# Arduino-DUE-V03.net
KiCad netlist of a schematic drawn in EAGLE
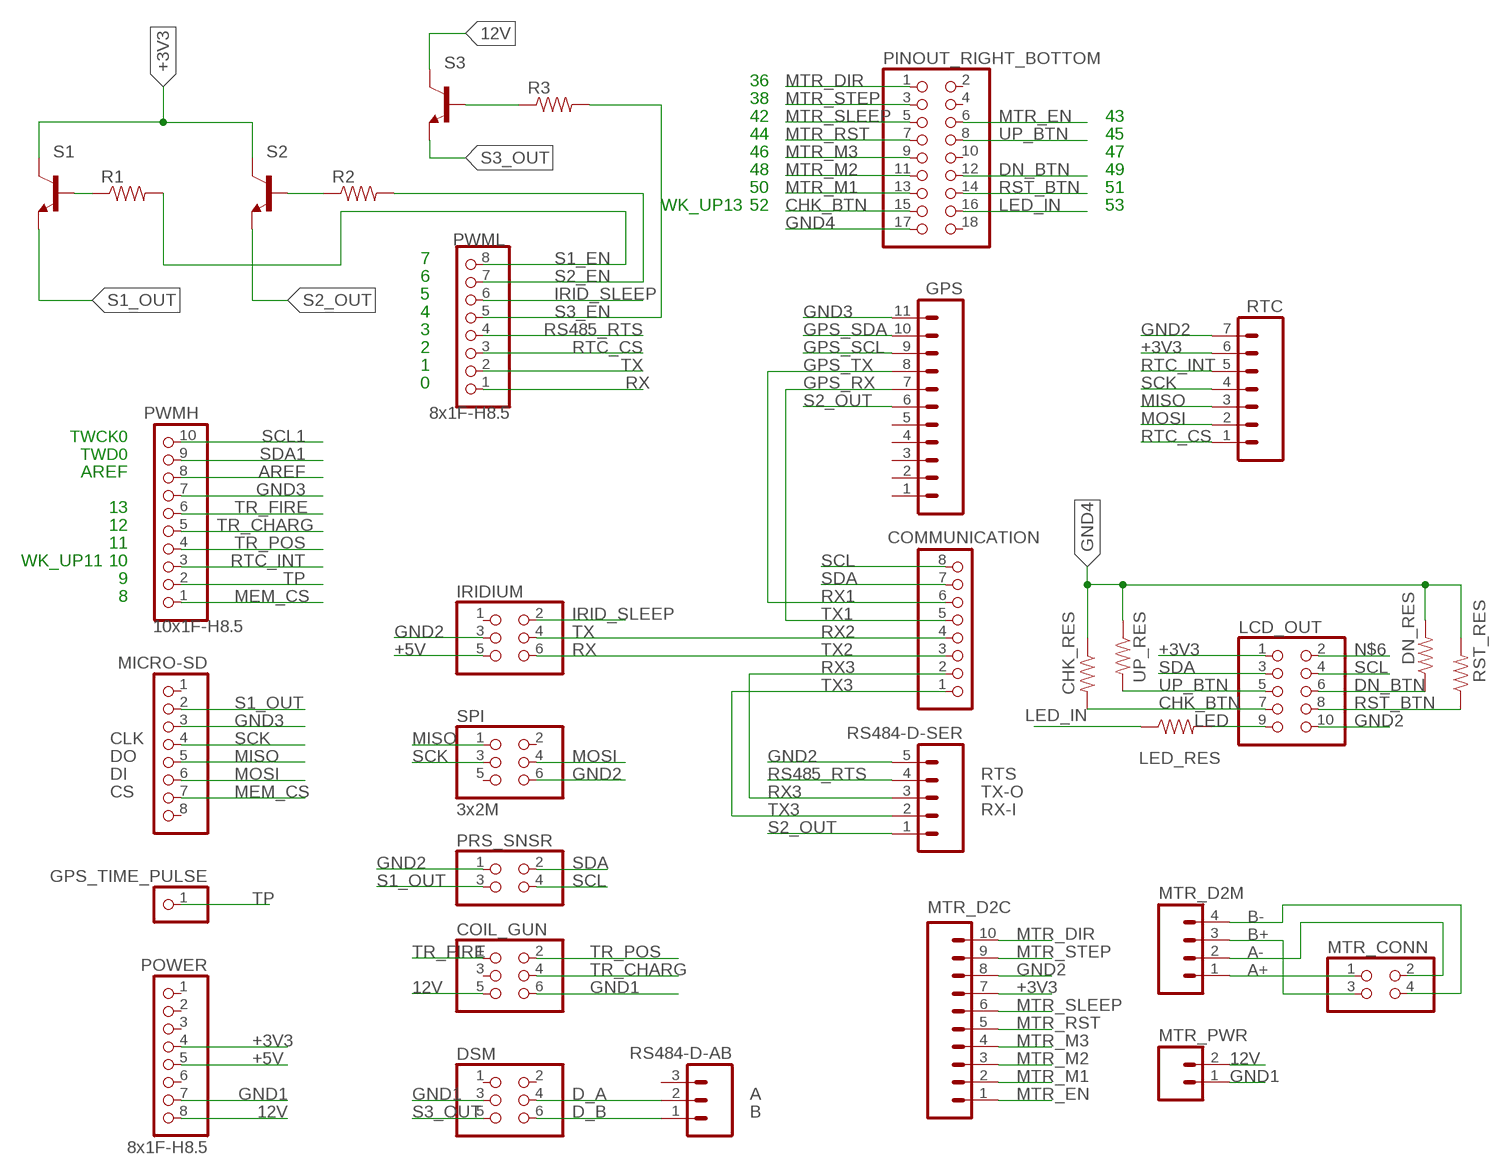
[diagram p0: schematic, sheet 1]

(export (version "E")
  (design (tool "Eeschema 10.0.6"))
  (components
    (comp (ref "CHK_RES")
      (value "RESISTORPTH-1/4W")
      (footprint "eagle-import:AXIAL-0.4")
      (libsource (lib "eagle-import") (part "RESISTORPTH-1/4W"))
    )
    (comp (ref "COIL_GUN")
      (value "PINHD-2X3")
      (footprint "eagle-import:2X03")
      (libsource (lib "eagle-import") (part "pinhead_PINHD-2X3"))
    )
    (comp (ref "COMMUNICATION")
      (value "8x1F-H8.5")
      (footprint "eagle-import:1X08")
      (libsource (lib "eagle-import") (part "PINHD-1X8"))
    )
    (comp (ref "DN_RES")
      (value "RESISTORPTH-1/4W")
      (footprint "eagle-import:AXIAL-0.4")
      (libsource (lib "eagle-import") (part "RESISTORPTH-1/4W"))
    )
    (comp (ref "DSM")
      (value "PINHD-2X3")
      (footprint "eagle-import:2X03")
      (libsource (lib "eagle-import") (part "pinhead_PINHD-2X3"))
    )
    (comp (ref "GPS")
      (value "M111.27MM")
      (footprint "eagle-import:1X11-1.27MM")
      (libsource (lib "eagle-import") (part "M111.27MM"))
    )
    (comp (ref "GPS_TIME_PULSE")
      (value "PINHD-1X1")
      (footprint "eagle-import:1X01")
      (libsource (lib "eagle-import") (part "PINHD-1X1"))
    )
    (comp (ref "IRIDIUM")
      (value "PINHD-2X3")
      (footprint "eagle-import:2X03")
      (libsource (lib "eagle-import") (part "pinhead_PINHD-2X3"))
    )
    (comp (ref "LCD_OUT")
      (value "PINHD-2X5")
      (footprint "eagle-import:2X05")
      (libsource (lib "eagle-import") (part "PINHD-2X5"))
    )
    (comp (ref "LED_RES")
      (value "RESISTORPTH-1/4W")
      (footprint "eagle-import:AXIAL-0.4")
      (libsource (lib "eagle-import") (part "RESISTORPTH-1/4W"))
    )
    (comp (ref "MICRO-SD")
      (value "PINHD-1X8BIG")
      (footprint "eagle-import:1X08-BIG")
      (libsource (lib "eagle-import") (part "PINHD-1X8BIG"))
    )
    (comp (ref "MTR_CONN")
      (value "PINHD-2X2")
      (footprint "eagle-import:2X02")
      (libsource (lib "eagle-import") (part "PINHD-2X2"))
    )
    (comp (ref "MTR_D2C")
      (value "M10SILK_FEMALE_PTH")
      (footprint "eagle-import:1X10")
      (libsource (lib "eagle-import") (part "M10SILK_FEMALE_PTH"))
    )
    (comp (ref "MTR_D2M")
      (value "M04NO_SILK_ALL_ROUND")
      (footprint "eagle-import:1X04_NO_SILK_ALL_ROUND")
      (libsource (lib "eagle-import") (part "M04NO_SILK_ALL_ROUND"))
    )
    (comp (ref "MTR_PWR")
      (value "M02PTH")
      (footprint "eagle-import:1X02")
      (libsource (lib "eagle-import") (part "M02PTH"))
    )
    (comp (ref "PINOUT_RIGHT_BOTTOM")
      (value "PINHD-2X9")
      (footprint "eagle-import:2X09")
      (libsource (lib "eagle-import") (part "PINHD-2X9"))
    )
    (comp (ref "POWER")
      (value "8x1F-H8.5")
      (footprint "eagle-import:1X08")
      (libsource (lib "eagle-import") (part "PINHD-1X8"))
    )
    (comp (ref "PRS_SNSR")
      (value "PINHD-2X2")
      (footprint "eagle-import:2X02")
      (libsource (lib "eagle-import") (part "PINHD-2X2"))
    )
    (comp (ref "PWMH")
      (value "10x1F-H8.5")
      (footprint "eagle-import:1X10")
      (libsource (lib "eagle-import") (part "PINHD-1X10"))
    )
    (comp (ref "PWML")
      (value "8x1F-H8.5")
      (footprint "eagle-import:1X08")
      (libsource (lib "eagle-import") (part "PINHD-1X8"))
    )
    (comp (ref "R1")
      (value "RESISTORPTH-1/4W")
      (footprint "eagle-import:AXIAL-0.4")
      (libsource (lib "eagle-import") (part "RESISTORPTH-1/4W"))
    )
    (comp (ref "R2")
      (value "RESISTORPTH-1/4W")
      (footprint "eagle-import:AXIAL-0.4")
      (libsource (lib "eagle-import") (part "RESISTORPTH-1/4W"))
    )
    (comp (ref "R3")
      (value "RESISTORPTH-1/4W")
      (footprint "eagle-import:AXIAL-0.4")
      (libsource (lib "eagle-import") (part "RESISTORPTH-1/4W"))
    )
    (comp (ref "RS484-D-AB")
      (value "M03PTH")
      (footprint "eagle-import:1X03")
      (libsource (lib "eagle-import") (part "M03PTH"))
    )
    (comp (ref "RS484-D-SER")
      (value "M05PTH")
      (footprint "eagle-import:1X05")
      (libsource (lib "eagle-import") (part "M05PTH"))
    )
    (comp (ref "RST_RES")
      (value "RESISTORPTH-1/4W")
      (footprint "eagle-import:AXIAL-0.4")
      (libsource (lib "eagle-import") (part "RESISTORPTH-1/4W"))
    )
    (comp (ref "RTC")
      (value "M07")
      (footprint "eagle-import:1X07")
      (libsource (lib "eagle-import") (part "M07"))
    )
    (comp (ref "S1")
      (value "2N3904")
      (footprint "eagle-import:TO92")
      (libsource (lib "eagle-import") (part "2N3904"))
    )
    (comp (ref "S2")
      (value "2N3904")
      (footprint "eagle-import:TO92")
      (libsource (lib "eagle-import") (part "2N3904"))
    )
    (comp (ref "S3")
      (value "2N3904")
      (footprint "eagle-import:TO92")
      (libsource (lib "eagle-import") (part "2N3904"))
    )
    (comp (ref "SPI")
      (value "3x2M")
      (footprint "eagle-import:2X03")
      (libsource (lib "eagle-import") (part "PINHD-2X3"))
    )
    (comp (ref "UP_RES")
      (value "RESISTORPTH-1/4W")
      (footprint "eagle-import:AXIAL-0.4")
      (libsource (lib "eagle-import") (part "RESISTORPTH-1/4W"))
    )
  )
  (nets
    (net (code "1") (name "+3V3") (class "Default")
      (node (ref "LCD_OUT") (pin "1") (pinfunction "1_1") (pintype "passive"))
      (node (ref "MTR_D2C") (pin "7") (pinfunction "7_7") (pintype "passive"))
      (node (ref "POWER") (pin "4") (pinfunction "4_4") (pintype "passive"))
      (node (ref "RTC") (pin "6") (pinfunction "6_6") (pintype "passive"))
      (node (ref "S1") (pin "1") (pinfunction "C_1") (pintype "passive"))
      (node (ref "S2") (pin "1") (pinfunction "C_1") (pintype "passive"))
    )
    (net (code "2") (name "/+5V") (class "Default")
      (node (ref "IRIDIUM") (pin "5") (pinfunction "5_5") (pintype "passive"))
      (node (ref "POWER") (pin "5") (pinfunction "5_5") (pintype "passive"))
    )
    (net (code "3") (name "/A+") (class "Default")
      (node (ref "MTR_CONN") (pin "1") (pinfunction "1_1") (pintype "passive"))
      (node (ref "MTR_D2M") (pin "1") (pinfunction "1_1") (pintype "passive"))
    )
    (net (code "4") (name "/A-") (class "Default")
      (node (ref "MTR_CONN") (pin "2") (pinfunction "2_2") (pintype "passive"))
      (node (ref "MTR_D2M") (pin "2") (pinfunction "2_2") (pintype "passive"))
    )
    (net (code "5") (name "/AREF") (class "Default")
      (node (ref "PWMH") (pin "8") (pinfunction "8_8") (pintype "passive"))
    )
    (net (code "6") (name "/B+") (class "Default")
      (node (ref "MTR_CONN") (pin "3") (pinfunction "3_3") (pintype "passive"))
      (node (ref "MTR_D2M") (pin "3") (pinfunction "3_3") (pintype "passive"))
    )
    (net (code "7") (name "/B-") (class "Default")
      (node (ref "MTR_CONN") (pin "4") (pinfunction "4_4") (pintype "passive"))
      (node (ref "MTR_D2M") (pin "4") (pinfunction "4_4") (pintype "passive"))
    )
    (net (code "8") (name "/CHK_BTN") (class "Default")
      (node (ref "CHK_RES") (pin "P$2") (pinfunction "2_P$2") (pintype "passive"))
      (node (ref "LCD_OUT") (pin "7") (pinfunction "7_7") (pintype "passive"))
      (node (ref "PINOUT_RIGHT_BOTTOM") (pin "15") (pinfunction "15_15") (pintype "passive"))
    )
    (net (code "9") (name "/DN_BTN") (class "Default")
      (node (ref "DN_RES") (pin "P$1") (pinfunction "1_P$1") (pintype "passive"))
      (node (ref "LCD_OUT") (pin "6") (pinfunction "6_6") (pintype "passive"))
      (node (ref "PINOUT_RIGHT_BOTTOM") (pin "12") (pinfunction "12_12") (pintype "passive"))
    )
    (net (code "10") (name "/D_A") (class "Default")
      (node (ref "DSM") (pin "4") (pinfunction "4_4") (pintype "passive"))
      (node (ref "RS484-D-AB") (pin "2") (pinfunction "2_2") (pintype "passive"))
    )
    (net (code "11") (name "/D_B") (class "Default")
      (node (ref "DSM") (pin "6") (pinfunction "6_6") (pintype "passive"))
      (node (ref "RS484-D-AB") (pin "1") (pinfunction "1_1") (pintype "passive"))
    )
    (net (code "12") (name "/GND1") (class "Default")
      (node (ref "COIL_GUN") (pin "6") (pinfunction "6_6") (pintype "passive"))
      (node (ref "DSM") (pin "3") (pinfunction "3_3") (pintype "passive"))
      (node (ref "MTR_PWR") (pin "1") (pinfunction "1_1") (pintype "passive"))
      (node (ref "POWER") (pin "7") (pinfunction "7_7") (pintype "passive"))
    )
    (net (code "13") (name "/GND2") (class "Default")
      (node (ref "IRIDIUM") (pin "3") (pinfunction "3_3") (pintype "passive"))
      (node (ref "LCD_OUT") (pin "10") (pinfunction "10_10") (pintype "passive"))
      (node (ref "MTR_D2C") (pin "8") (pinfunction "8_8") (pintype "passive"))
      (node (ref "PRS_SNSR") (pin "1") (pinfunction "1_1") (pintype "passive"))
      (node (ref "RS484-D-SER") (pin "5") (pinfunction "5_5") (pintype "passive"))
      (node (ref "RTC") (pin "7") (pinfunction "7_7") (pintype "passive"))
      (node (ref "SPI") (pin "6") (pinfunction "6_6") (pintype "passive"))
    )
    (net (code "14") (name "/GND3") (class "Default")
      (node (ref "GPS") (pin "11") (pinfunction "11_11") (pintype "passive"))
      (node (ref "MICRO-SD") (pin "3") (pinfunction "3_3") (pintype "passive"))
      (node (ref "PWMH") (pin "7") (pinfunction "7_7") (pintype "passive"))
    )
    (net (code "15") (name "/GPS_RX") (class "Default")
      (node (ref "COMMUNICATION") (pin "5") (pinfunction "5_5") (pintype "passive"))
      (node (ref "GPS") (pin "7") (pinfunction "7_7") (pintype "passive"))
    )
    (net (code "16") (name "/GPS_SCL") (class "Default")
      (node (ref "GPS") (pin "9") (pinfunction "9_9") (pintype "passive"))
    )
    (net (code "17") (name "/GPS_SDA") (class "Default")
      (node (ref "GPS") (pin "10") (pinfunction "10_10") (pintype "passive"))
    )
    (net (code "18") (name "/GPS_TX") (class "Default")
      (node (ref "COMMUNICATION") (pin "6") (pinfunction "6_6") (pintype "passive"))
      (node (ref "GPS") (pin "8") (pinfunction "8_8") (pintype "passive"))
    )
    (net (code "19") (name "/IRID_SLEEP") (class "Default")
      (node (ref "IRIDIUM") (pin "2") (pinfunction "2_2") (pintype "passive"))
      (node (ref "PWML") (pin "6") (pinfunction "6_6") (pintype "passive"))
    )
    (net (code "20") (name "/LED") (class "Default")
      (node (ref "LCD_OUT") (pin "9") (pinfunction "9_9") (pintype "passive"))
      (node (ref "LED_RES") (pin "P$2") (pinfunction "2_P$2") (pintype "passive"))
    )
    (net (code "21") (name "/LED_IN") (class "Default")
      (node (ref "LED_RES") (pin "P$1") (pinfunction "1_P$1") (pintype "passive"))
      (node (ref "PINOUT_RIGHT_BOTTOM") (pin "16") (pinfunction "16_16") (pintype "passive"))
    )
    (net (code "22") (name "/MEM_CS") (class "Default")
      (node (ref "MICRO-SD") (pin "7") (pinfunction "7_7") (pintype "passive"))
      (node (ref "PWMH") (pin "1") (pinfunction "1_1") (pintype "passive"))
    )
    (net (code "23") (name "/MISO") (class "Default")
      (node (ref "MICRO-SD") (pin "5") (pinfunction "5_5") (pintype "passive"))
      (node (ref "RTC") (pin "3") (pinfunction "3_3") (pintype "passive"))
      (node (ref "SPI") (pin "1") (pinfunction "1_1") (pintype "passive"))
    )
    (net (code "24") (name "/MOSI") (class "Default")
      (node (ref "MICRO-SD") (pin "6") (pinfunction "6_6") (pintype "passive"))
      (node (ref "RTC") (pin "2") (pinfunction "2_2") (pintype "passive"))
      (node (ref "SPI") (pin "4") (pinfunction "4_4") (pintype "passive"))
    )
    (net (code "25") (name "/MTR_DIR") (class "Default")
      (node (ref "MTR_D2C") (pin "10") (pinfunction "10_10") (pintype "passive"))
      (node (ref "PINOUT_RIGHT_BOTTOM") (pin "1") (pinfunction "1_1") (pintype "passive"))
    )
    (net (code "26") (name "/MTR_EN") (class "Default")
      (node (ref "MTR_D2C") (pin "1") (pinfunction "1_1") (pintype "passive"))
      (node (ref "PINOUT_RIGHT_BOTTOM") (pin "6") (pinfunction "6_6") (pintype "passive"))
    )
    (net (code "27") (name "/MTR_M1") (class "Default")
      (node (ref "MTR_D2C") (pin "2") (pinfunction "2_2") (pintype "passive"))
      (node (ref "PINOUT_RIGHT_BOTTOM") (pin "13") (pinfunction "13_13") (pintype "passive"))
    )
    (net (code "28") (name "/MTR_M2") (class "Default")
      (node (ref "MTR_D2C") (pin "3") (pinfunction "3_3") (pintype "passive"))
      (node (ref "PINOUT_RIGHT_BOTTOM") (pin "11") (pinfunction "11_11") (pintype "passive"))
    )
    (net (code "29") (name "/MTR_M3") (class "Default")
      (node (ref "MTR_D2C") (pin "4") (pinfunction "4_4") (pintype "passive"))
      (node (ref "PINOUT_RIGHT_BOTTOM") (pin "9") (pinfunction "9_9") (pintype "passive"))
    )
    (net (code "30") (name "/MTR_RST") (class "Default")
      (node (ref "MTR_D2C") (pin "5") (pinfunction "5_5") (pintype "passive"))
      (node (ref "PINOUT_RIGHT_BOTTOM") (pin "7") (pinfunction "7_7") (pintype "passive"))
    )
    (net (code "31") (name "/MTR_SLEEP") (class "Default")
      (node (ref "MTR_D2C") (pin "6") (pinfunction "6_6") (pintype "passive"))
      (node (ref "PINOUT_RIGHT_BOTTOM") (pin "5") (pinfunction "5_5") (pintype "passive"))
    )
    (net (code "32") (name "/MTR_STEP") (class "Default")
      (node (ref "MTR_D2C") (pin "9") (pinfunction "9_9") (pintype "passive"))
      (node (ref "PINOUT_RIGHT_BOTTOM") (pin "3") (pinfunction "3_3") (pintype "passive"))
    )
    (net (code "33") (name "/N$6") (class "Default")
      (node (ref "LCD_OUT") (pin "2") (pinfunction "2_2") (pintype "passive"))
    )
    (net (code "34") (name "/RS485_RTS") (class "Default")
      (node (ref "PWML") (pin "4") (pinfunction "4_4") (pintype "passive"))
      (node (ref "RS484-D-SER") (pin "4") (pinfunction "4_4") (pintype "passive"))
    )
    (net (code "35") (name "/RST_BTN") (class "Default")
      (node (ref "LCD_OUT") (pin "8") (pinfunction "8_8") (pintype "passive"))
      (node (ref "PINOUT_RIGHT_BOTTOM") (pin "14") (pinfunction "14_14") (pintype "passive"))
      (node (ref "RST_RES") (pin "P$1") (pinfunction "1_P$1") (pintype "passive"))
    )
    (net (code "36") (name "/RTC_CS") (class "Default")
      (node (ref "PWML") (pin "3") (pinfunction "3_3") (pintype "passive"))
      (node (ref "RTC") (pin "1") (pinfunction "1_1") (pintype "passive"))
    )
    (net (code "37") (name "/RTC_INT") (class "Default")
      (node (ref "PWMH") (pin "3") (pinfunction "3_3") (pintype "passive"))
      (node (ref "RTC") (pin "5") (pinfunction "5_5") (pintype "passive"))
    )
    (net (code "38") (name "/RX") (class "Default")
      (node (ref "PWML") (pin "1") (pinfunction "1_1") (pintype "passive"))
    )
    (net (code "39") (name "/RX2") (class "Default")
      (node (ref "COMMUNICATION") (pin "4") (pinfunction "4_4") (pintype "passive"))
      (node (ref "IRIDIUM") (pin "4") (pinfunction "4_4") (pintype "passive"))
    )
    (net (code "40") (name "/RX3") (class "Default")
      (node (ref "COMMUNICATION") (pin "2") (pinfunction "2_2") (pintype "passive"))
      (node (ref "RS484-D-SER") (pin "3") (pinfunction "3_3") (pintype "passive"))
    )
    (net (code "41") (name "/S1_EN") (class "Default")
      (node (ref "PWML") (pin "8") (pinfunction "8_8") (pintype "passive"))
      (node (ref "R1") (pin "P$2") (pinfunction "2_P$2") (pintype "passive"))
    )
    (net (code "42") (name "/S2_EN") (class "Default")
      (node (ref "PWML") (pin "7") (pinfunction "7_7") (pintype "passive"))
      (node (ref "R2") (pin "P$2") (pinfunction "2_P$2") (pintype "passive"))
    )
    (net (code "43") (name "/S3_EN") (class "Default")
      (node (ref "PWML") (pin "5") (pinfunction "5_5") (pintype "passive"))
      (node (ref "R3") (pin "P$2") (pinfunction "2_P$2") (pintype "passive"))
    )
    (net (code "44") (name "/SCK") (class "Default")
      (node (ref "MICRO-SD") (pin "4") (pinfunction "4_4") (pintype "passive"))
      (node (ref "RTC") (pin "4") (pinfunction "4_4") (pintype "passive"))
      (node (ref "SPI") (pin "3") (pinfunction "3_3") (pintype "passive"))
    )
    (net (code "45") (name "/SCL") (class "Default")
      (node (ref "COMMUNICATION") (pin "8") (pinfunction "8_8") (pintype "passive"))
      (node (ref "LCD_OUT") (pin "4") (pinfunction "4_4") (pintype "passive"))
      (node (ref "PRS_SNSR") (pin "4") (pinfunction "4_4") (pintype "passive"))
    )
    (net (code "46") (name "/SCL1") (class "Default")
      (node (ref "PWMH") (pin "10") (pinfunction "10_10") (pintype "passive"))
    )
    (net (code "47") (name "/SDA") (class "Default")
      (node (ref "COMMUNICATION") (pin "7") (pinfunction "7_7") (pintype "passive"))
      (node (ref "LCD_OUT") (pin "3") (pinfunction "3_3") (pintype "passive"))
      (node (ref "PRS_SNSR") (pin "2") (pinfunction "2_2") (pintype "passive"))
    )
    (net (code "48") (name "/SDA1") (class "Default")
      (node (ref "PWMH") (pin "9") (pinfunction "9_9") (pintype "passive"))
    )
    (net (code "49") (name "/TP") (class "Default")
      (node (ref "GPS_TIME_PULSE") (pin "1") (pinfunction "1_1") (pintype "passive"))
      (node (ref "PWMH") (pin "2") (pinfunction "2_2") (pintype "passive"))
    )
    (net (code "50") (name "/TR_CHARG") (class "Default")
      (node (ref "COIL_GUN") (pin "4") (pinfunction "4_4") (pintype "passive"))
      (node (ref "PWMH") (pin "5") (pinfunction "5_5") (pintype "passive"))
    )
    (net (code "51") (name "/TR_FIRE") (class "Default")
      (node (ref "COIL_GUN") (pin "1") (pinfunction "1_1") (pintype "passive"))
      (node (ref "PWMH") (pin "6") (pinfunction "6_6") (pintype "passive"))
    )
    (net (code "52") (name "/TR_POS") (class "Default")
      (node (ref "COIL_GUN") (pin "2") (pinfunction "2_2") (pintype "passive"))
      (node (ref "PWMH") (pin "4") (pinfunction "4_4") (pintype "passive"))
    )
    (net (code "53") (name "/TX") (class "Default")
      (node (ref "PWML") (pin "2") (pinfunction "2_2") (pintype "passive"))
    )
    (net (code "54") (name "/TX2") (class "Default")
      (node (ref "COMMUNICATION") (pin "3") (pinfunction "3_3") (pintype "passive"))
      (node (ref "IRIDIUM") (pin "6") (pinfunction "6_6") (pintype "passive"))
    )
    (net (code "55") (name "/TX3") (class "Default")
      (node (ref "COMMUNICATION") (pin "1") (pinfunction "1_1") (pintype "passive"))
      (node (ref "RS484-D-SER") (pin "2") (pinfunction "2_2") (pintype "passive"))
    )
    (net (code "56") (name "/UP_BTN") (class "Default")
      (node (ref "LCD_OUT") (pin "5") (pinfunction "5_5") (pintype "passive"))
      (node (ref "PINOUT_RIGHT_BOTTOM") (pin "8") (pinfunction "8_8") (pintype "passive"))
      (node (ref "UP_RES") (pin "P$2") (pinfunction "2_P$2") (pintype "passive"))
    )
    (net (code "57") (name "12V") (class "Default")
      (node (ref "COIL_GUN") (pin "5") (pinfunction "5_5") (pintype "passive"))
      (node (ref "MTR_PWR") (pin "2") (pinfunction "2_2") (pintype "passive"))
      (node (ref "POWER") (pin "8") (pinfunction "8_8") (pintype "passive"))
      (node (ref "S3") (pin "1") (pinfunction "C_1") (pintype "passive"))
    )
    (net (code "58") (name "GND4") (class "Default")
      (node (ref "CHK_RES") (pin "P$1") (pinfunction "1_P$1") (pintype "passive"))
      (node (ref "DN_RES") (pin "P$2") (pinfunction "2_P$2") (pintype "passive"))
      (node (ref "PINOUT_RIGHT_BOTTOM") (pin "17") (pinfunction "17_17") (pintype "passive"))
      (node (ref "RST_RES") (pin "P$2") (pinfunction "2_P$2") (pintype "passive"))
      (node (ref "UP_RES") (pin "P$1") (pinfunction "1_P$1") (pintype "passive"))
    )
    (net (code "59") (name "Net-(R1-1)") (class "Default")
      (node (ref "R1") (pin "P$1") (pinfunction "1_P$1") (pintype "passive"))
      (node (ref "S1") (pin "2") (pinfunction "B_2") (pintype "passive"))
    )
    (net (code "60") (name "Net-(R2-1)") (class "Default")
      (node (ref "R2") (pin "P$1") (pinfunction "1_P$1") (pintype "passive"))
      (node (ref "S2") (pin "2") (pinfunction "B_2") (pintype "passive"))
    )
    (net (code "61") (name "Net-(R3-1)") (class "Default")
      (node (ref "R3") (pin "P$1") (pinfunction "1_P$1") (pintype "passive"))
      (node (ref "S3") (pin "2") (pinfunction "B_2") (pintype "passive"))
    )
    (net (code "62") (name "S1_OUT") (class "Default")
      (node (ref "MICRO-SD") (pin "2") (pinfunction "2_2") (pintype "passive"))
      (node (ref "PRS_SNSR") (pin "3") (pinfunction "3_3") (pintype "passive"))
      (node (ref "S1") (pin "3") (pinfunction "E_3") (pintype "passive"))
    )
    (net (code "63") (name "S2_OUT") (class "Default")
      (node (ref "GPS") (pin "6") (pinfunction "6_6") (pintype "passive"))
      (node (ref "RS484-D-SER") (pin "1") (pinfunction "1_1") (pintype "passive"))
      (node (ref "S2") (pin "3") (pinfunction "E_3") (pintype "passive"))
    )
    (net (code "64") (name "S3_OUT") (class "Default")
      (node (ref "DSM") (pin "5") (pinfunction "5_5") (pintype "passive"))
      (node (ref "S3") (pin "3") (pinfunction "E_3") (pintype "passive"))
    )
    (net (code "65") (name "unconnected-(COIL_GUN-Pad3)") (class "Default")
      (node (ref "COIL_GUN") (pin "3") (pinfunction "3_3") (pintype "passive"))
    )
    (net (code "66") (name "unconnected-(DSM-Pad1)") (class "Default")
      (node (ref "DSM") (pin "1") (pinfunction "1_1") (pintype "passive"))
    )
    (net (code "67") (name "unconnected-(DSM-Pad2)") (class "Default")
      (node (ref "DSM") (pin "2") (pinfunction "2_2") (pintype "passive"))
    )
    (net (code "68") (name "unconnected-(GPS-Pad1)") (class "Default")
      (node (ref "GPS") (pin "1") (pinfunction "1_1") (pintype "passive"))
    )
    (net (code "69") (name "unconnected-(GPS-Pad2)") (class "Default")
      (node (ref "GPS") (pin "2") (pinfunction "2_2") (pintype "passive"))
    )
    (net (code "70") (name "unconnected-(GPS-Pad3)") (class "Default")
      (node (ref "GPS") (pin "3") (pinfunction "3_3") (pintype "passive"))
    )
    (net (code "71") (name "unconnected-(GPS-Pad4)") (class "Default")
      (node (ref "GPS") (pin "4") (pinfunction "4_4") (pintype "passive"))
    )
    (net (code "72") (name "unconnected-(GPS-Pad5)") (class "Default")
      (node (ref "GPS") (pin "5") (pinfunction "5_5") (pintype "passive"))
    )
    (net (code "73") (name "unconnected-(IRIDIUM-Pad1)") (class "Default")
      (node (ref "IRIDIUM") (pin "1") (pinfunction "1_1") (pintype "passive"))
    )
    (net (code "74") (name "unconnected-(MICRO-SD-Pad1)") (class "Default")
      (node (ref "MICRO-SD") (pin "1") (pinfunction "1_1") (pintype "passive"))
    )
    (net (code "75") (name "unconnected-(MICRO-SD-Pad8)") (class "Default")
      (node (ref "MICRO-SD") (pin "8") (pinfunction "8_8") (pintype "passive"))
    )
    (net (code "76") (name "unconnected-(PINOUT_RIGHT_BOTTOM-Pad2)") (class "Default")
      (node (ref "PINOUT_RIGHT_BOTTOM") (pin "2") (pinfunction "2_2") (pintype "passive"))
    )
    (net (code "77") (name "unconnected-(PINOUT_RIGHT_BOTTOM-Pad4)") (class "Default")
      (node (ref "PINOUT_RIGHT_BOTTOM") (pin "4") (pinfunction "4_4") (pintype "passive"))
    )
    (net (code "78") (name "unconnected-(PINOUT_RIGHT_BOTTOM-Pad10)") (class "Default")
      (node (ref "PINOUT_RIGHT_BOTTOM") (pin "10") (pinfunction "10_10") (pintype "passive"))
    )
    (net (code "79") (name "unconnected-(PINOUT_RIGHT_BOTTOM-Pad18)") (class "Default")
      (node (ref "PINOUT_RIGHT_BOTTOM") (pin "18") (pinfunction "18_18") (pintype "passive"))
    )
    (net (code "80") (name "unconnected-(POWER-Pad1)") (class "Default")
      (node (ref "POWER") (pin "1") (pinfunction "1_1") (pintype "passive"))
    )
    (net (code "81") (name "unconnected-(POWER-Pad2)") (class "Default")
      (node (ref "POWER") (pin "2") (pinfunction "2_2") (pintype "passive"))
    )
    (net (code "82") (name "unconnected-(POWER-Pad3)") (class "Default")
      (node (ref "POWER") (pin "3") (pinfunction "3_3") (pintype "passive"))
    )
    (net (code "83") (name "unconnected-(POWER-Pad6)") (class "Default")
      (node (ref "POWER") (pin "6") (pinfunction "6_6") (pintype "passive"))
    )
    (net (code "84") (name "unconnected-(RS484-D-AB-Pad3)") (class "Default")
      (node (ref "RS484-D-AB") (pin "3") (pinfunction "3_3") (pintype "passive"))
    )
    (net (code "85") (name "unconnected-(SPI-Pad2)") (class "Default")
      (node (ref "SPI") (pin "2") (pinfunction "2_2") (pintype "passive"))
    )
    (net (code "86") (name "unconnected-(SPI-Pad5)") (class "Default")
      (node (ref "SPI") (pin "5") (pinfunction "5_5") (pintype "passive"))
    )
  )
)
